# displayBoard.net
KiCad netlist of a schematic drawn in EAGLE
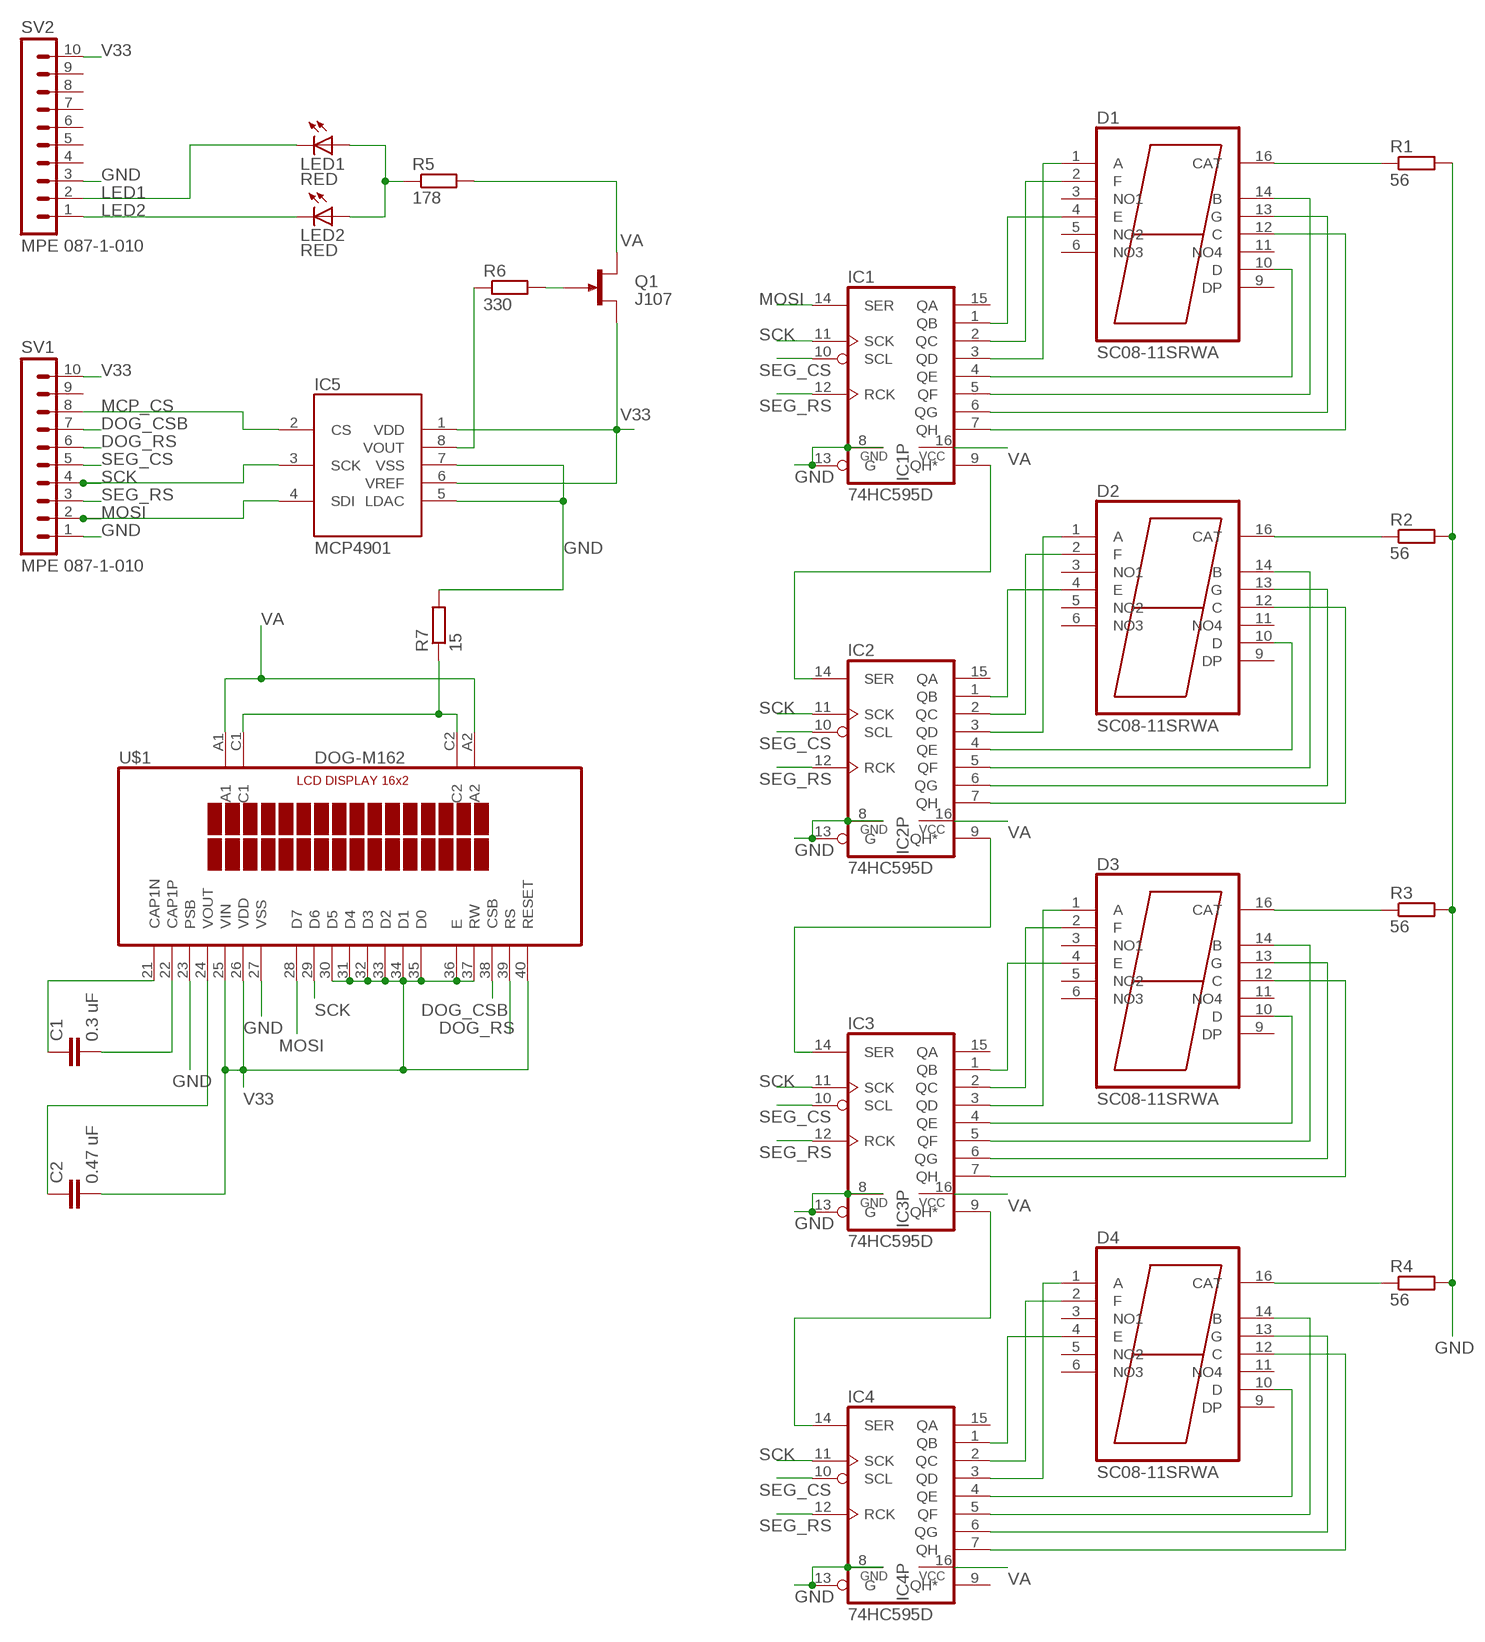
[diagram p0: schematic, sheet 1]

(export (version "E")
  (design (tool "Eeschema 10.0.6"))
  (components
    (comp (ref "C1")
      (value "0.3 uF")
      (footprint "eagle-import:C1206")
      (libsource (lib "eagle-import") (part "C-EUC1206"))
    )
    (comp (ref "C2")
      (value "0.47 uF")
      (footprint "eagle-import:C1206")
      (libsource (lib "eagle-import") (part "C-EUC1206"))
    )
    (comp (ref "D1")
      (value "SC08-11SRWA")
      (footprint "eagle-import:SC08-11SRWA")
      (libsource (lib "eagle-import") (part "SC08-11SRWA"))
    )
    (comp (ref "D2")
      (value "SC08-11SRWA")
      (footprint "eagle-import:SC08-11SRWA")
      (libsource (lib "eagle-import") (part "SC08-11SRWA"))
    )
    (comp (ref "D3")
      (value "SC08-11SRWA")
      (footprint "eagle-import:SC08-11SRWA")
      (libsource (lib "eagle-import") (part "SC08-11SRWA"))
    )
    (comp (ref "D4")
      (value "SC08-11SRWA")
      (footprint "eagle-import:SC08-11SRWA")
      (libsource (lib "eagle-import") (part "SC08-11SRWA"))
    )
    (comp (ref "IC1")
      (value "74HC595D")
      (footprint "eagle-import:SO16")
      (libsource (lib "eagle-import") (part "74595DHC"))
    )
    (comp (ref "IC2")
      (value "74HC595D")
      (footprint "eagle-import:SO16")
      (libsource (lib "eagle-import") (part "74595DHC"))
    )
    (comp (ref "IC3")
      (value "74HC595D")
      (footprint "eagle-import:SO16")
      (libsource (lib "eagle-import") (part "74595DHC"))
    )
    (comp (ref "IC4")
      (value "74HC595D")
      (footprint "eagle-import:SO16")
      (libsource (lib "eagle-import") (part "74595DHC"))
    )
    (comp (ref "IC5")
      (value "MCP4901")
      (footprint "eagle-import:MSOP8")
      (libsource (lib "eagle-import") (part "MCP4901"))
    )
    (comp (ref "LED1")
      (value "RED")
      (footprint "eagle-import:LED3MM")
      (libsource (lib "eagle-import") (part "LED3MM"))
    )
    (comp (ref "LED2")
      (value "RED")
      (footprint "eagle-import:LED3MM")
      (libsource (lib "eagle-import") (part "LED3MM"))
    )
    (comp (ref "Q1")
      (value "J107")
      (footprint "eagle-import:TO92R")
      (libsource (lib "eagle-import") (part "J105"))
    )
    (comp (ref "R1")
      (value "56")
      (footprint "eagle-import:R1206")
      (libsource (lib "eagle-import") (part "R-EU_R1206"))
    )
    (comp (ref "R2")
      (value "56")
      (footprint "eagle-import:R1206")
      (libsource (lib "eagle-import") (part "R-EU_R1206"))
    )
    (comp (ref "R3")
      (value "56")
      (footprint "eagle-import:R1206")
      (libsource (lib "eagle-import") (part "R-EU_R1206"))
    )
    (comp (ref "R4")
      (value "56")
      (footprint "eagle-import:R1206")
      (libsource (lib "eagle-import") (part "R-EU_R1206"))
    )
    (comp (ref "R5")
      (value "178")
      (footprint "eagle-import:R1206")
      (libsource (lib "eagle-import") (part "R-EU_R1206"))
    )
    (comp (ref "R6")
      (value "330")
      (footprint "eagle-import:R1206")
      (libsource (lib "eagle-import") (part "R-EU_R1206"))
    )
    (comp (ref "R7")
      (value "15")
      (footprint "eagle-import:R1206")
      (libsource (lib "eagle-import") (part "R-EU_R1206"))
    )
    (comp (ref "SV1")
      (value "MPE 087-1-010")
      (footprint "eagle-import:MA10-1")
      (libsource (lib "eagle-import") (part "MA10-1"))
    )
    (comp (ref "SV2")
      (value "MPE 087-1-010")
      (footprint "eagle-import:MA10-1")
      (libsource (lib "eagle-import") (part "MA10-1"))
    )
    (comp (ref "U$1")
      (value "DOG-M162")
      (footprint "eagle-import:DOGM162")
      (libsource (lib "eagle-import") (part "DOG-M162"))
    )
  )
  (nets
    (net (code "1") (name "/DOG_CSB") (class "Default")
      (node (ref "SV1") (pin "7") (pinfunction "7_7") (pintype "passive"))
      (node (ref "U$1") (pin "38") (pinfunction "CSB_38") (pintype "bidirectional"))
    )
    (net (code "2") (name "/DOG_RS") (class "Default")
      (node (ref "SV1") (pin "6") (pinfunction "6_6") (pintype "passive"))
      (node (ref "U$1") (pin "39") (pinfunction "RS_39") (pintype "bidirectional"))
    )
    (net (code "3") (name "/GND") (class "Default")
      (node (ref "IC1") (pin "13") (pinfunction "G_13") (pintype "input"))
      (node (ref "IC1") (pin "8") (pinfunction "GND_8") (pintype "power_in"))
      (node (ref "IC2") (pin "13") (pinfunction "G_13") (pintype "input"))
      (node (ref "IC2") (pin "8") (pinfunction "GND_8") (pintype "power_in"))
      (node (ref "IC3") (pin "13") (pinfunction "G_13") (pintype "input"))
      (node (ref "IC3") (pin "8") (pinfunction "GND_8") (pintype "power_in"))
      (node (ref "IC4") (pin "13") (pinfunction "G_13") (pintype "input"))
      (node (ref "IC4") (pin "8") (pinfunction "GND_8") (pintype "power_in"))
      (node (ref "IC5") (pin "5") (pinfunction "LDAC_5") (pintype "bidirectional"))
      (node (ref "IC5") (pin "7") (pinfunction "VSS_7") (pintype "power_in"))
      (node (ref "R1") (pin "2") (pinfunction "2_2") (pintype "passive"))
      (node (ref "R2") (pin "2") (pinfunction "2_2") (pintype "passive"))
      (node (ref "R3") (pin "2") (pinfunction "2_2") (pintype "passive"))
      (node (ref "R4") (pin "2") (pinfunction "2_2") (pintype "passive"))
      (node (ref "R7") (pin "2") (pinfunction "2_2") (pintype "passive"))
      (node (ref "SV1") (pin "1") (pinfunction "1_1") (pintype "passive"))
      (node (ref "SV2") (pin "3") (pinfunction "3_3") (pintype "passive"))
      (node (ref "U$1") (pin "23") (pinfunction "PSB_23") (pintype "power_in"))
      (node (ref "U$1") (pin "27") (pinfunction "VSS_27") (pintype "power_in"))
    )
    (net (code "4") (name "/LED1") (class "Default")
      (node (ref "LED1") (pin "K") (pinfunction "C_K") (pintype "passive"))
      (node (ref "SV2") (pin "2") (pinfunction "2_2") (pintype "passive"))
    )
    (net (code "5") (name "/LED2") (class "Default")
      (node (ref "LED2") (pin "K") (pinfunction "C_K") (pintype "passive"))
      (node (ref "SV2") (pin "1") (pinfunction "1_1") (pintype "passive"))
    )
    (net (code "6") (name "/MCP_CS") (class "Default")
      (node (ref "IC5") (pin "2") (pinfunction "CS_2") (pintype "bidirectional"))
      (node (ref "SV1") (pin "8") (pinfunction "8_8") (pintype "passive"))
    )
    (net (code "7") (name "/MOSI") (class "Default")
      (node (ref "IC1") (pin "14") (pinfunction "SER_14") (pintype "input"))
      (node (ref "IC5") (pin "4") (pinfunction "SDI_4") (pintype "bidirectional"))
      (node (ref "SV1") (pin "2") (pinfunction "2_2") (pintype "passive"))
      (node (ref "U$1") (pin "28") (pinfunction "D7_28") (pintype "bidirectional"))
    )
    (net (code "8") (name "/SCK") (class "Default")
      (node (ref "IC1") (pin "11") (pinfunction "SCK_11") (pintype "input"))
      (node (ref "IC2") (pin "11") (pinfunction "SCK_11") (pintype "input"))
      (node (ref "IC3") (pin "11") (pinfunction "SCK_11") (pintype "input"))
      (node (ref "IC4") (pin "11") (pinfunction "SCK_11") (pintype "input"))
      (node (ref "IC5") (pin "3") (pinfunction "SCK_3") (pintype "bidirectional"))
      (node (ref "SV1") (pin "4") (pinfunction "4_4") (pintype "passive"))
      (node (ref "U$1") (pin "29") (pinfunction "D6_29") (pintype "bidirectional"))
    )
    (net (code "9") (name "/SEG_CS") (class "Default")
      (node (ref "IC1") (pin "10") (pinfunction "SCL_10") (pintype "input"))
      (node (ref "IC2") (pin "10") (pinfunction "SCL_10") (pintype "input"))
      (node (ref "IC3") (pin "10") (pinfunction "SCL_10") (pintype "input"))
      (node (ref "IC4") (pin "10") (pinfunction "SCL_10") (pintype "input"))
      (node (ref "SV1") (pin "5") (pinfunction "5_5") (pintype "passive"))
    )
    (net (code "10") (name "/SEG_RS") (class "Default")
      (node (ref "IC1") (pin "12") (pinfunction "RCK_12") (pintype "input"))
      (node (ref "IC2") (pin "12") (pinfunction "RCK_12") (pintype "input"))
      (node (ref "IC3") (pin "12") (pinfunction "RCK_12") (pintype "input"))
      (node (ref "IC4") (pin "12") (pinfunction "RCK_12") (pintype "input"))
      (node (ref "SV1") (pin "3") (pinfunction "3_3") (pintype "passive"))
    )
    (net (code "11") (name "/V33") (class "Default")
      (node (ref "C2") (pin "2") (pinfunction "2_2") (pintype "passive"))
      (node (ref "IC5") (pin "1") (pinfunction "VDD_1") (pintype "power_in"))
      (node (ref "IC5") (pin "6") (pinfunction "VREF_6") (pintype "bidirectional"))
      (node (ref "Q1") (pin "S") (pinfunction "S_S") (pintype "passive"))
      (node (ref "SV1") (pin "10") (pinfunction "10_10") (pintype "passive"))
      (node (ref "SV2") (pin "10") (pinfunction "10_10") (pintype "passive"))
      (node (ref "U$1") (pin "25") (pinfunction "VIN_25") (pintype "bidirectional"))
      (node (ref "U$1") (pin "26") (pinfunction "VDD_26") (pintype "power_in"))
      (node (ref "U$1") (pin "30") (pinfunction "D5_30") (pintype "bidirectional"))
      (node (ref "U$1") (pin "31") (pinfunction "D4_31") (pintype "bidirectional"))
      (node (ref "U$1") (pin "32") (pinfunction "D3_32") (pintype "bidirectional"))
      (node (ref "U$1") (pin "33") (pinfunction "D2_33") (pintype "bidirectional"))
      (node (ref "U$1") (pin "34") (pinfunction "D1_34") (pintype "bidirectional"))
      (node (ref "U$1") (pin "35") (pinfunction "D0_35") (pintype "bidirectional"))
      (node (ref "U$1") (pin "36") (pinfunction "E_36") (pintype "bidirectional"))
      (node (ref "U$1") (pin "37") (pinfunction "RW_37") (pintype "bidirectional"))
      (node (ref "U$1") (pin "40") (pinfunction "RESET_40") (pintype "bidirectional"))
    )
    (net (code "12") (name "/VA") (class "Default")
      (node (ref "IC1") (pin "16") (pinfunction "VCC_16") (pintype "power_in"))
      (node (ref "IC2") (pin "16") (pinfunction "VCC_16") (pintype "power_in"))
      (node (ref "IC3") (pin "16") (pinfunction "VCC_16") (pintype "power_in"))
      (node (ref "IC4") (pin "16") (pinfunction "VCC_16") (pintype "power_in"))
      (node (ref "Q1") (pin "D") (pinfunction "D_D") (pintype "passive"))
      (node (ref "R5") (pin "2") (pinfunction "2_2") (pintype "passive"))
      (node (ref "U$1") (pin "A1") (pinfunction "A1_A1") (pintype "bidirectional"))
      (node (ref "U$1") (pin "A2") (pinfunction "A2_A2") (pintype "bidirectional"))
    )
    (net (code "13") (name "Net-(D1-A)") (class "Default")
      (node (ref "D1") (pin "1") (pinfunction "A_1") (pintype "input"))
      (node (ref "IC1") (pin "3") (pinfunction "QD_3") (pintype "tri_state"))
    )
    (net (code "14") (name "Net-(D1-B)") (class "Default")
      (node (ref "D1") (pin "14") (pinfunction "B_14") (pintype "input"))
      (node (ref "IC1") (pin "5") (pinfunction "QF_5") (pintype "tri_state"))
    )
    (net (code "15") (name "Net-(D1-C)") (class "Default")
      (node (ref "D1") (pin "12") (pinfunction "C_12") (pintype "input"))
      (node (ref "IC1") (pin "7") (pinfunction "QH_7") (pintype "tri_state"))
    )
    (net (code "16") (name "Net-(D1-CAT)") (class "Default")
      (node (ref "D1") (pin "16") (pinfunction "CAT_16") (pintype "bidirectional"))
      (node (ref "R1") (pin "1") (pinfunction "1_1") (pintype "passive"))
    )
    (net (code "17") (name "Net-(D1-D)") (class "Default")
      (node (ref "D1") (pin "10") (pinfunction "D_10") (pintype "input"))
      (node (ref "IC1") (pin "4") (pinfunction "QE_4") (pintype "tri_state"))
    )
    (net (code "18") (name "Net-(D1-E)") (class "Default")
      (node (ref "D1") (pin "4") (pinfunction "E_4") (pintype "input"))
      (node (ref "IC1") (pin "1") (pinfunction "QB_1") (pintype "tri_state"))
    )
    (net (code "19") (name "Net-(D1-F)") (class "Default")
      (node (ref "D1") (pin "2") (pinfunction "F_2") (pintype "input"))
      (node (ref "IC1") (pin "2") (pinfunction "QC_2") (pintype "tri_state"))
    )
    (net (code "20") (name "Net-(D1-G)") (class "Default")
      (node (ref "D1") (pin "13") (pinfunction "G_13") (pintype "input"))
      (node (ref "IC1") (pin "6") (pinfunction "QG_6") (pintype "tri_state"))
    )
    (net (code "21") (name "Net-(D2-A)") (class "Default")
      (node (ref "D2") (pin "1") (pinfunction "A_1") (pintype "input"))
      (node (ref "IC2") (pin "3") (pinfunction "QD_3") (pintype "tri_state"))
    )
    (net (code "22") (name "Net-(D2-B)") (class "Default")
      (node (ref "D2") (pin "14") (pinfunction "B_14") (pintype "input"))
      (node (ref "IC2") (pin "5") (pinfunction "QF_5") (pintype "tri_state"))
    )
    (net (code "23") (name "Net-(D2-C)") (class "Default")
      (node (ref "D2") (pin "12") (pinfunction "C_12") (pintype "input"))
      (node (ref "IC2") (pin "7") (pinfunction "QH_7") (pintype "tri_state"))
    )
    (net (code "24") (name "Net-(D2-CAT)") (class "Default")
      (node (ref "D2") (pin "16") (pinfunction "CAT_16") (pintype "bidirectional"))
      (node (ref "R2") (pin "1") (pinfunction "1_1") (pintype "passive"))
    )
    (net (code "25") (name "Net-(D2-D)") (class "Default")
      (node (ref "D2") (pin "10") (pinfunction "D_10") (pintype "input"))
      (node (ref "IC2") (pin "4") (pinfunction "QE_4") (pintype "tri_state"))
    )
    (net (code "26") (name "Net-(D2-E)") (class "Default")
      (node (ref "D2") (pin "4") (pinfunction "E_4") (pintype "input"))
      (node (ref "IC2") (pin "1") (pinfunction "QB_1") (pintype "tri_state"))
    )
    (net (code "27") (name "Net-(D2-F)") (class "Default")
      (node (ref "D2") (pin "2") (pinfunction "F_2") (pintype "input"))
      (node (ref "IC2") (pin "2") (pinfunction "QC_2") (pintype "tri_state"))
    )
    (net (code "28") (name "Net-(D2-G)") (class "Default")
      (node (ref "D2") (pin "13") (pinfunction "G_13") (pintype "input"))
      (node (ref "IC2") (pin "6") (pinfunction "QG_6") (pintype "tri_state"))
    )
    (net (code "29") (name "Net-(D3-A)") (class "Default")
      (node (ref "D3") (pin "1") (pinfunction "A_1") (pintype "input"))
      (node (ref "IC3") (pin "3") (pinfunction "QD_3") (pintype "tri_state"))
    )
    (net (code "30") (name "Net-(D3-B)") (class "Default")
      (node (ref "D3") (pin "14") (pinfunction "B_14") (pintype "input"))
      (node (ref "IC3") (pin "5") (pinfunction "QF_5") (pintype "tri_state"))
    )
    (net (code "31") (name "Net-(D3-C)") (class "Default")
      (node (ref "D3") (pin "12") (pinfunction "C_12") (pintype "input"))
      (node (ref "IC3") (pin "7") (pinfunction "QH_7") (pintype "tri_state"))
    )
    (net (code "32") (name "Net-(D3-CAT)") (class "Default")
      (node (ref "D3") (pin "16") (pinfunction "CAT_16") (pintype "bidirectional"))
      (node (ref "R3") (pin "1") (pinfunction "1_1") (pintype "passive"))
    )
    (net (code "33") (name "Net-(D3-D)") (class "Default")
      (node (ref "D3") (pin "10") (pinfunction "D_10") (pintype "input"))
      (node (ref "IC3") (pin "4") (pinfunction "QE_4") (pintype "tri_state"))
    )
    (net (code "34") (name "Net-(D3-E)") (class "Default")
      (node (ref "D3") (pin "4") (pinfunction "E_4") (pintype "input"))
      (node (ref "IC3") (pin "1") (pinfunction "QB_1") (pintype "tri_state"))
    )
    (net (code "35") (name "Net-(D3-F)") (class "Default")
      (node (ref "D3") (pin "2") (pinfunction "F_2") (pintype "input"))
      (node (ref "IC3") (pin "2") (pinfunction "QC_2") (pintype "tri_state"))
    )
    (net (code "36") (name "Net-(D3-G)") (class "Default")
      (node (ref "D3") (pin "13") (pinfunction "G_13") (pintype "input"))
      (node (ref "IC3") (pin "6") (pinfunction "QG_6") (pintype "tri_state"))
    )
    (net (code "37") (name "Net-(D4-A)") (class "Default")
      (node (ref "D4") (pin "1") (pinfunction "A_1") (pintype "input"))
      (node (ref "IC4") (pin "3") (pinfunction "QD_3") (pintype "tri_state"))
    )
    (net (code "38") (name "Net-(D4-B)") (class "Default")
      (node (ref "D4") (pin "14") (pinfunction "B_14") (pintype "input"))
      (node (ref "IC4") (pin "5") (pinfunction "QF_5") (pintype "tri_state"))
    )
    (net (code "39") (name "Net-(D4-C)") (class "Default")
      (node (ref "D4") (pin "12") (pinfunction "C_12") (pintype "input"))
      (node (ref "IC4") (pin "7") (pinfunction "QH_7") (pintype "tri_state"))
    )
    (net (code "40") (name "Net-(D4-CAT)") (class "Default")
      (node (ref "D4") (pin "16") (pinfunction "CAT_16") (pintype "bidirectional"))
      (node (ref "R4") (pin "1") (pinfunction "1_1") (pintype "passive"))
    )
    (net (code "41") (name "Net-(D4-D)") (class "Default")
      (node (ref "D4") (pin "10") (pinfunction "D_10") (pintype "input"))
      (node (ref "IC4") (pin "4") (pinfunction "QE_4") (pintype "tri_state"))
    )
    (net (code "42") (name "Net-(D4-E)") (class "Default")
      (node (ref "D4") (pin "4") (pinfunction "E_4") (pintype "input"))
      (node (ref "IC4") (pin "1") (pinfunction "QB_1") (pintype "tri_state"))
    )
    (net (code "43") (name "Net-(D4-F)") (class "Default")
      (node (ref "D4") (pin "2") (pinfunction "F_2") (pintype "input"))
      (node (ref "IC4") (pin "2") (pinfunction "QC_2") (pintype "tri_state"))
    )
    (net (code "44") (name "Net-(D4-G)") (class "Default")
      (node (ref "D4") (pin "13") (pinfunction "G_13") (pintype "input"))
      (node (ref "IC4") (pin "6") (pinfunction "QG_6") (pintype "tri_state"))
    )
    (net (code "45") (name "Net-(IC1A-QH*)") (class "Default")
      (node (ref "IC1") (pin "9") (pinfunction "QH*_9") (pintype "tri_state"))
      (node (ref "IC2") (pin "14") (pinfunction "SER_14") (pintype "input"))
    )
    (net (code "46") (name "Net-(IC2A-QH*)") (class "Default")
      (node (ref "IC2") (pin "9") (pinfunction "QH*_9") (pintype "tri_state"))
      (node (ref "IC3") (pin "14") (pinfunction "SER_14") (pintype "input"))
    )
    (net (code "47") (name "Net-(IC3A-QH*)") (class "Default")
      (node (ref "IC3") (pin "9") (pinfunction "QH*_9") (pintype "tri_state"))
      (node (ref "IC4") (pin "14") (pinfunction "SER_14") (pintype "input"))
    )
    (net (code "48") (name "Net-(IC5-VOUT)") (class "Default")
      (node (ref "IC5") (pin "8") (pinfunction "VOUT_8") (pintype "bidirectional"))
      (node (ref "R6") (pin "1") (pinfunction "1_1") (pintype "passive"))
    )
    (net (code "49") (name "Net-(LED1-PadA)") (class "Default")
      (node (ref "LED1") (pin "A") (pinfunction "A_A") (pintype "passive"))
      (node (ref "LED2") (pin "A") (pinfunction "A_A") (pintype "passive"))
      (node (ref "R5") (pin "1") (pinfunction "1_1") (pintype "passive"))
    )
    (net (code "50") (name "Net-(Q1-PadG)") (class "Default")
      (node (ref "Q1") (pin "G") (pinfunction "G_G") (pintype "passive"))
      (node (ref "R6") (pin "2") (pinfunction "2_2") (pintype "passive"))
    )
    (net (code "51") (name "Net-(R7-Pad1)") (class "Default")
      (node (ref "R7") (pin "1") (pinfunction "1_1") (pintype "passive"))
      (node (ref "U$1") (pin "C1") (pinfunction "C1_C1") (pintype "bidirectional"))
      (node (ref "U$1") (pin "C2") (pinfunction "C2_C2") (pintype "bidirectional"))
    )
    (net (code "52") (name "Net-(U$1-CAP1N)") (class "Default")
      (node (ref "C1") (pin "1") (pinfunction "1_1") (pintype "passive"))
      (node (ref "U$1") (pin "21") (pinfunction "CAP1N_21") (pintype "bidirectional"))
    )
    (net (code "53") (name "Net-(U$1-CAP1P)") (class "Default")
      (node (ref "C1") (pin "2") (pinfunction "2_2") (pintype "passive"))
      (node (ref "U$1") (pin "22") (pinfunction "CAP1P_22") (pintype "bidirectional"))
    )
    (net (code "54") (name "Net-(U$1-VOUT)") (class "Default")
      (node (ref "C2") (pin "1") (pinfunction "1_1") (pintype "passive"))
      (node (ref "U$1") (pin "24") (pinfunction "VOUT_24") (pintype "bidirectional"))
    )
    (net (code "55") (name "unconnected-(D1-DP-Pad9)") (class "Default")
      (node (ref "D1") (pin "9") (pinfunction "DP_9") (pintype "bidirectional"))
    )
    (net (code "56") (name "unconnected-(D1-NO1-Pad3)") (class "Default")
      (node (ref "D1") (pin "3") (pinfunction "NO1_3") (pintype "bidirectional"))
    )
    (net (code "57") (name "unconnected-(D1-NO2-Pad5)") (class "Default")
      (node (ref "D1") (pin "5") (pinfunction "NO2_5") (pintype "bidirectional"))
    )
    (net (code "58") (name "unconnected-(D1-NO3-Pad6)") (class "Default")
      (node (ref "D1") (pin "6") (pinfunction "NO3_6") (pintype "bidirectional"))
    )
    (net (code "59") (name "unconnected-(D1-NO4-Pad11)") (class "Default")
      (node (ref "D1") (pin "11") (pinfunction "NO4_11") (pintype "bidirectional"))
    )
    (net (code "60") (name "unconnected-(D2-DP-Pad9)") (class "Default")
      (node (ref "D2") (pin "9") (pinfunction "DP_9") (pintype "bidirectional"))
    )
    (net (code "61") (name "unconnected-(D2-NO1-Pad3)") (class "Default")
      (node (ref "D2") (pin "3") (pinfunction "NO1_3") (pintype "bidirectional"))
    )
    (net (code "62") (name "unconnected-(D2-NO2-Pad5)") (class "Default")
      (node (ref "D2") (pin "5") (pinfunction "NO2_5") (pintype "bidirectional"))
    )
    (net (code "63") (name "unconnected-(D2-NO3-Pad6)") (class "Default")
      (node (ref "D2") (pin "6") (pinfunction "NO3_6") (pintype "bidirectional"))
    )
    (net (code "64") (name "unconnected-(D2-NO4-Pad11)") (class "Default")
      (node (ref "D2") (pin "11") (pinfunction "NO4_11") (pintype "bidirectional"))
    )
    (net (code "65") (name "unconnected-(D3-DP-Pad9)") (class "Default")
      (node (ref "D3") (pin "9") (pinfunction "DP_9") (pintype "bidirectional"))
    )
    (net (code "66") (name "unconnected-(D3-NO1-Pad3)") (class "Default")
      (node (ref "D3") (pin "3") (pinfunction "NO1_3") (pintype "bidirectional"))
    )
    (net (code "67") (name "unconnected-(D3-NO2-Pad5)") (class "Default")
      (node (ref "D3") (pin "5") (pinfunction "NO2_5") (pintype "bidirectional"))
    )
    (net (code "68") (name "unconnected-(D3-NO3-Pad6)") (class "Default")
      (node (ref "D3") (pin "6") (pinfunction "NO3_6") (pintype "bidirectional"))
    )
    (net (code "69") (name "unconnected-(D3-NO4-Pad11)") (class "Default")
      (node (ref "D3") (pin "11") (pinfunction "NO4_11") (pintype "bidirectional"))
    )
    (net (code "70") (name "unconnected-(D4-DP-Pad9)") (class "Default")
      (node (ref "D4") (pin "9") (pinfunction "DP_9") (pintype "bidirectional"))
    )
    (net (code "71") (name "unconnected-(D4-NO1-Pad3)") (class "Default")
      (node (ref "D4") (pin "3") (pinfunction "NO1_3") (pintype "bidirectional"))
    )
    (net (code "72") (name "unconnected-(D4-NO2-Pad5)") (class "Default")
      (node (ref "D4") (pin "5") (pinfunction "NO2_5") (pintype "bidirectional"))
    )
    (net (code "73") (name "unconnected-(D4-NO3-Pad6)") (class "Default")
      (node (ref "D4") (pin "6") (pinfunction "NO3_6") (pintype "bidirectional"))
    )
    (net (code "74") (name "unconnected-(D4-NO4-Pad11)") (class "Default")
      (node (ref "D4") (pin "11") (pinfunction "NO4_11") (pintype "bidirectional"))
    )
    (net (code "75") (name "unconnected-(IC1A-QA-Pad15)") (class "Default")
      (node (ref "IC1") (pin "15") (pinfunction "QA_15") (pintype "tri_state"))
    )
    (net (code "76") (name "unconnected-(IC2A-QA-Pad15)") (class "Default")
      (node (ref "IC2") (pin "15") (pinfunction "QA_15") (pintype "tri_state"))
    )
    (net (code "77") (name "unconnected-(IC3A-QA-Pad15)") (class "Default")
      (node (ref "IC3") (pin "15") (pinfunction "QA_15") (pintype "tri_state"))
    )
    (net (code "78") (name "unconnected-(IC4A-QA-Pad15)") (class "Default")
      (node (ref "IC4") (pin "15") (pinfunction "QA_15") (pintype "tri_state"))
    )
    (net (code "79") (name "unconnected-(IC4A-QH*-Pad9)") (class "Default")
      (node (ref "IC4") (pin "9") (pinfunction "QH*_9") (pintype "tri_state"))
    )
    (net (code "80") (name "unconnected-(SV1-Pad9)") (class "Default")
      (node (ref "SV1") (pin "9") (pinfunction "9_9") (pintype "passive"))
    )
    (net (code "81") (name "unconnected-(SV2-Pad4)") (class "Default")
      (node (ref "SV2") (pin "4") (pinfunction "4_4") (pintype "passive"))
    )
    (net (code "82") (name "unconnected-(SV2-Pad5)") (class "Default")
      (node (ref "SV2") (pin "5") (pinfunction "5_5") (pintype "passive"))
    )
    (net (code "83") (name "unconnected-(SV2-Pad6)") (class "Default")
      (node (ref "SV2") (pin "6") (pinfunction "6_6") (pintype "passive"))
    )
    (net (code "84") (name "unconnected-(SV2-Pad7)") (class "Default")
      (node (ref "SV2") (pin "7") (pinfunction "7_7") (pintype "passive"))
    )
    (net (code "85") (name "unconnected-(SV2-Pad8)") (class "Default")
      (node (ref "SV2") (pin "8") (pinfunction "8_8") (pintype "passive"))
    )
    (net (code "86") (name "unconnected-(SV2-Pad9)") (class "Default")
      (node (ref "SV2") (pin "9") (pinfunction "9_9") (pintype "passive"))
    )
  )
)
